# atmega328_tlc5940.net
KiCad netlist of a schematic drawn in EAGLE
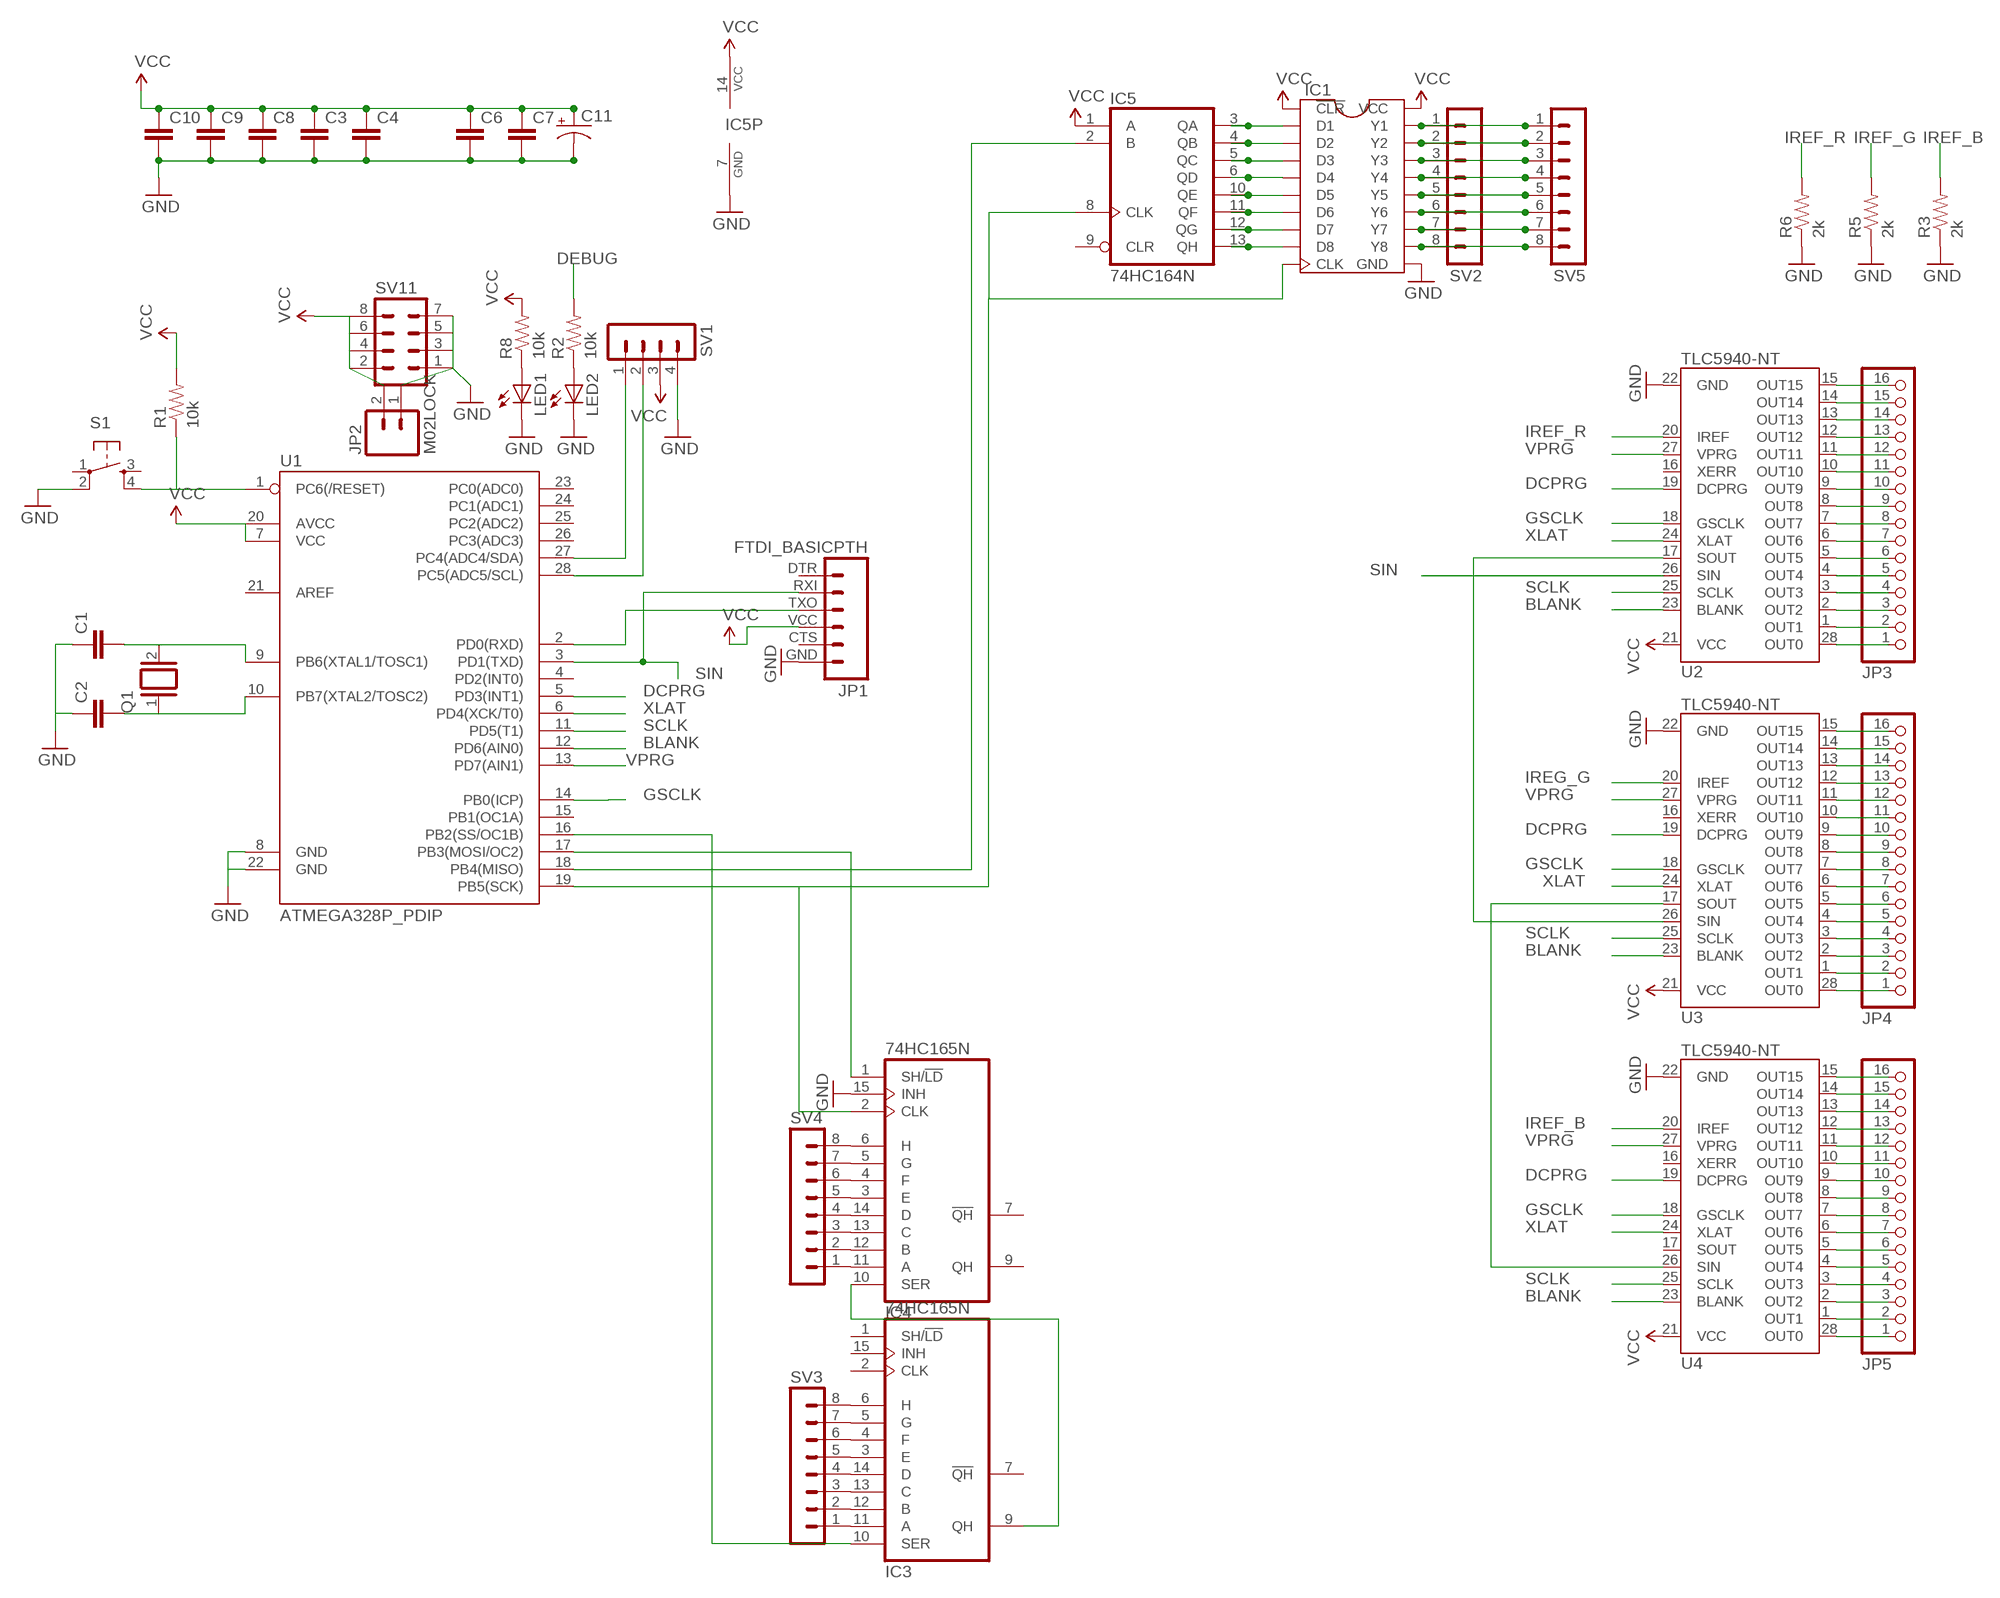
[diagram p0: schematic, sheet 1]

(export (version "E")
  (design (tool "Eeschema 10.0.6"))
  (components
    (comp (ref "C1")
      (value "CAPEZ")
      (footprint "eagle-import:CAP-PTH-SMALLEZ")
      (libsource (lib "eagle-import") (part "SparkFun-Passives_CAPEZ"))
    )
    (comp (ref "C2")
      (value "CAPEZ")
      (footprint "eagle-import:CAP-PTH-SMALLEZ")
      (libsource (lib "eagle-import") (part "SparkFun-Passives_CAPEZ"))
    )
    (comp (ref "C3")
      (value "CAPEZ")
      (footprint "eagle-import:CAP-PTH-SMALLEZ")
      (libsource (lib "eagle-import") (part "CAPEZ"))
    )
    (comp (ref "C4")
      (value "CAPEZ")
      (footprint "eagle-import:CAP-PTH-SMALLEZ")
      (libsource (lib "eagle-import") (part "CAPEZ"))
    )
    (comp (ref "C6")
      (value "CAPEZ")
      (footprint "eagle-import:CAP-PTH-SMALLEZ")
      (libsource (lib "eagle-import") (part "CAPEZ"))
    )
    (comp (ref "C7")
      (value "CAPEZ")
      (footprint "eagle-import:CAP-PTH-SMALLEZ")
      (libsource (lib "eagle-import") (part "CAPEZ"))
    )
    (comp (ref "C8")
      (value "CAPEZ")
      (footprint "eagle-import:CAP-PTH-SMALLEZ")
      (libsource (lib "eagle-import") (part "CAPEZ"))
    )
    (comp (ref "C9")
      (value "CAPEZ")
      (footprint "eagle-import:CAP-PTH-SMALLEZ")
      (libsource (lib "eagle-import") (part "CAPEZ"))
    )
    (comp (ref "C10")
      (value "CAPEZ")
      (footprint "eagle-import:CAP-PTH-SMALLEZ")
      (libsource (lib "eagle-import") (part "CAPEZ"))
    )
    (comp (ref "C11")
      (value "CPOL-USE3.5-8")
      (footprint "eagle-import:E3,5-8")
      (libsource (lib "eagle-import") (part "CPOL-USE3.5-8"))
    )
    (comp (ref "IC1")
      (value "IC-PACKAGE_DIL20S")
      (footprint "eagle-import:IC-PACKAGE_SOCKET-20")
      (libsource (lib "eagle-import") (part "IC-PACKAGE_DIL20S"))
    )
    (comp (ref "IC3")
      (value "74HC165N")
      (footprint "eagle-import:DIL16")
      (libsource (lib "eagle-import") (part "74165NHC"))
    )
    (comp (ref "IC4")
      (value "74HC165N")
      (footprint "eagle-import:DIL16")
      (libsource (lib "eagle-import") (part "74165NHC"))
    )
    (comp (ref "IC5")
      (value "74HC164N")
      (footprint "eagle-import:DIL14")
      (libsource (lib "eagle-import") (part "74164NHC"))
    )
    (comp (ref "JP1")
      (value "FTDI_BASICPTH")
      (footprint "eagle-import:FTDI_BASIC")
      (libsource (lib "eagle-import") (part "FTDI_BASICPTH"))
    )
    (comp (ref "JP2")
      (value "M02LOCK")
      (footprint "eagle-import:1X02_LOCK")
      (libsource (lib "eagle-import") (part "M02LOCK"))
    )
    (comp (ref "JP3")
      (value "PINHD-1X16")
      (footprint "eagle-import:1X16")
      (libsource (lib "eagle-import") (part "PINHD-1X16"))
    )
    (comp (ref "JP4")
      (value "PINHD-1X16")
      (footprint "eagle-import:1X16")
      (libsource (lib "eagle-import") (part "PINHD-1X16"))
    )
    (comp (ref "JP5")
      (value "PINHD-1X16")
      (footprint "eagle-import:1X16")
      (libsource (lib "eagle-import") (part "PINHD-1X16"))
    )
    (comp (ref "LED1")
      (value "LED5MM")
      (footprint "eagle-import:LED5MM")
      (libsource (lib "eagle-import") (part "LED5MM"))
    )
    (comp (ref "LED2")
      (value "LED5MM")
      (footprint "eagle-import:LED5MM")
      (libsource (lib "eagle-import") (part "LED5MM"))
    )
    (comp (ref "Q1")
      (value "XTAL/S")
      (footprint "eagle-import:QS")
      (libsource (lib "eagle-import") (part "XTAL/S"))
    )
    (comp (ref "R1")
      (value "10k")
      (footprint "eagle-import:AXIAL-0.3-KIT")
      (libsource (lib "eagle-import") (part "RESISTORKIT"))
    )
    (comp (ref "R2")
      (value "10k")
      (footprint "eagle-import:AXIAL-0.3-KIT")
      (libsource (lib "eagle-import") (part "RESISTORKIT"))
    )
    (comp (ref "R3")
      (value "2k")
      (footprint "eagle-import:AXIAL-0.3-KIT")
      (libsource (lib "eagle-import") (part "RESISTORKIT"))
    )
    (comp (ref "R5")
      (value "2k")
      (footprint "eagle-import:AXIAL-0.3-KIT")
      (libsource (lib "eagle-import") (part "RESISTORKIT"))
    )
    (comp (ref "R6")
      (value "2k")
      (footprint "eagle-import:AXIAL-0.3-KIT")
      (libsource (lib "eagle-import") (part "RESISTORKIT"))
    )
    (comp (ref "R8")
      (value "10k")
      (footprint "eagle-import:AXIAL-0.3-KIT")
      (libsource (lib "eagle-import") (part "RESISTORKIT"))
    )
    (comp (ref "S1")
      (value "TAC_SWITCHPTH")
      (footprint "eagle-import:TACTILE-PTH")
      (libsource (lib "eagle-import") (part "TAC_SWITCHPTH"))
    )
    (comp (ref "SV1")
      (value "MA04-1")
      (footprint "eagle-import:MA04-1")
      (libsource (lib "eagle-import") (part "MA04-1"))
    )
    (comp (ref "SV2")
      (value "MA08-1")
      (footprint "eagle-import:MA08-1")
      (libsource (lib "eagle-import") (part "MA08-1"))
    )
    (comp (ref "SV3")
      (value "MA08-1")
      (footprint "eagle-import:MA08-1")
      (libsource (lib "eagle-import") (part "MA08-1"))
    )
    (comp (ref "SV4")
      (value "MA08-1")
      (footprint "eagle-import:MA08-1")
      (libsource (lib "eagle-import") (part "MA08-1"))
    )
    (comp (ref "SV5")
      (value "MA08-1")
      (footprint "eagle-import:MA08-1")
      (libsource (lib "eagle-import") (part "MA08-1"))
    )
    (comp (ref "SV11")
      (value "MA04-2")
      (footprint "eagle-import:MA04-2")
      (libsource (lib "eagle-import") (part "MA04-2"))
    )
    (comp (ref "U1")
      (value "ATMEGA328P_PDIP")
      (footprint "eagle-import:DIL28-3")
      (libsource (lib "eagle-import") (part "ATMEGA328P_PDIP"))
    )
    (comp (ref "U2")
      (value "TLC5940-NT")
      (footprint "eagle-import:DIL28-3")
      (libsource (lib "eagle-import") (part "TLC5940-NT"))
    )
    (comp (ref "U3")
      (value "TLC5940-NT")
      (footprint "eagle-import:DIL28-3")
      (libsource (lib "eagle-import") (part "TLC5940-NT"))
    )
    (comp (ref "U4")
      (value "TLC5940-NT")
      (footprint "eagle-import:DIL28-3")
      (libsource (lib "eagle-import") (part "TLC5940-NT"))
    )
  )
  (nets
    (net (code "1") (name "/BLANK") (class "Default")
      (node (ref "U1") (pin "12") (pinfunction "PD6(AIN0)_12") (pintype "bidirectional"))
      (node (ref "U2") (pin "23") (pinfunction "BLANK_23") (pintype "bidirectional"))
      (node (ref "U3") (pin "23") (pinfunction "BLANK_23") (pintype "bidirectional"))
      (node (ref "U4") (pin "23") (pinfunction "BLANK_23") (pintype "bidirectional"))
    )
    (net (code "2") (name "/DCPRG") (class "Default")
      (node (ref "U1") (pin "5") (pinfunction "PD3(INT1)_5") (pintype "bidirectional"))
      (node (ref "U2") (pin "19") (pinfunction "DCPRG_19") (pintype "bidirectional"))
      (node (ref "U3") (pin "19") (pinfunction "DCPRG_19") (pintype "bidirectional"))
      (node (ref "U4") (pin "19") (pinfunction "DCPRG_19") (pintype "bidirectional"))
    )
    (net (code "3") (name "/DEBUG") (class "Default")
      (node (ref "R2") (pin "P$2") (pinfunction "2_P$2") (pintype "passive"))
    )
    (net (code "4") (name "/GSCLK") (class "Default")
      (node (ref "U1") (pin "14") (pinfunction "PB0(ICP)_14") (pintype "bidirectional"))
      (node (ref "U2") (pin "18") (pinfunction "GSCLK_18") (pintype "bidirectional"))
      (node (ref "U3") (pin "18") (pinfunction "GSCLK_18") (pintype "bidirectional"))
      (node (ref "U4") (pin "18") (pinfunction "GSCLK_18") (pintype "bidirectional"))
    )
    (net (code "5") (name "/IREF_B") (class "Default")
      (node (ref "R3") (pin "P$2") (pinfunction "2_P$2") (pintype "passive"))
      (node (ref "U4") (pin "20") (pinfunction "IREF_20") (pintype "bidirectional"))
    )
    (net (code "6") (name "/IREF_G") (class "Default")
      (node (ref "R5") (pin "P$2") (pinfunction "2_P$2") (pintype "passive"))
    )
    (net (code "7") (name "/IREF_R") (class "Default")
      (node (ref "R6") (pin "P$2") (pinfunction "2_P$2") (pintype "passive"))
      (node (ref "U2") (pin "20") (pinfunction "IREF_20") (pintype "bidirectional"))
    )
    (net (code "8") (name "/IREG_G") (class "Default")
      (node (ref "U3") (pin "20") (pinfunction "IREF_20") (pintype "bidirectional"))
    )
    (net (code "9") (name "/SCLK") (class "Default")
      (node (ref "U1") (pin "11") (pinfunction "PD5(T1)_11") (pintype "bidirectional"))
      (node (ref "U2") (pin "25") (pinfunction "SCLK_25") (pintype "bidirectional"))
      (node (ref "U3") (pin "25") (pinfunction "SCLK_25") (pintype "bidirectional"))
      (node (ref "U4") (pin "25") (pinfunction "SCLK_25") (pintype "bidirectional"))
    )
    (net (code "10") (name "/SIN") (class "Default")
      (node (ref "JP1") (pin "RXI") (pinfunction "2_RXI") (pintype "passive"))
      (node (ref "U1") (pin "3") (pinfunction "PD1(TXD)_3") (pintype "bidirectional"))
      (node (ref "U2") (pin "26") (pinfunction "SIN_26") (pintype "bidirectional"))
    )
    (net (code "11") (name "/VPRG") (class "Default")
      (node (ref "U1") (pin "13") (pinfunction "PD7(AIN1)_13") (pintype "bidirectional"))
      (node (ref "U2") (pin "27") (pinfunction "VPRG_27") (pintype "bidirectional"))
      (node (ref "U3") (pin "27") (pinfunction "VPRG_27") (pintype "bidirectional"))
      (node (ref "U4") (pin "27") (pinfunction "VPRG_27") (pintype "bidirectional"))
    )
    (net (code "12") (name "/XLAT") (class "Default")
      (node (ref "U1") (pin "6") (pinfunction "PD4(XCK/T0)_6") (pintype "bidirectional"))
      (node (ref "U2") (pin "24") (pinfunction "XLAT_24") (pintype "bidirectional"))
      (node (ref "U3") (pin "24") (pinfunction "XLAT_24") (pintype "bidirectional"))
      (node (ref "U4") (pin "24") (pinfunction "XLAT_24") (pintype "bidirectional"))
    )
    (net (code "13") (name "GND") (class "Default")
      (node (ref "C1") (pin "1") (pinfunction "1_1") (pintype "passive"))
      (node (ref "C10") (pin "2") (pinfunction "2_2") (pintype "passive"))
      (node (ref "C11") (pin "-") (pinfunction "-_-") (pintype "passive"))
      (node (ref "C2") (pin "1") (pinfunction "1_1") (pintype "passive"))
      (node (ref "C3") (pin "2") (pinfunction "2_2") (pintype "passive"))
      (node (ref "C4") (pin "2") (pinfunction "2_2") (pintype "passive"))
      (node (ref "C6") (pin "2") (pinfunction "2_2") (pintype "passive"))
      (node (ref "C7") (pin "2") (pinfunction "2_2") (pintype "passive"))
      (node (ref "C8") (pin "2") (pinfunction "2_2") (pintype "passive"))
      (node (ref "C9") (pin "2") (pinfunction "2_2") (pintype "passive"))
      (node (ref "IC1") (pin "11") (pinfunction "GND_11") (pintype "power_in"))
      (node (ref "IC4") (pin "15") (pinfunction "INH_15") (pintype "input"))
      (node (ref "IC5") (pin "7") (pinfunction "GND_7") (pintype "power_in"))
      (node (ref "JP1") (pin "GND") (pinfunction "6_GND") (pintype "passive"))
      (node (ref "JP2") (pin "1") (pinfunction "1_1") (pintype "passive"))
      (node (ref "LED1") (pin "K") (pinfunction "C_K") (pintype "passive"))
      (node (ref "LED2") (pin "K") (pinfunction "C_K") (pintype "passive"))
      (node (ref "R3") (pin "P$1") (pinfunction "1_P$1") (pintype "passive"))
      (node (ref "R5") (pin "P$1") (pinfunction "1_P$1") (pintype "passive"))
      (node (ref "R6") (pin "P$1") (pinfunction "1_P$1") (pintype "passive"))
      (node (ref "S1") (pin "2") (pinfunction "2_2") (pintype "passive"))
      (node (ref "SV1") (pin "4") (pinfunction "4_4") (pintype "passive"))
      (node (ref "SV11") (pin "1") (pinfunction "1_1") (pintype "passive"))
      (node (ref "SV11") (pin "3") (pinfunction "3_3") (pintype "passive"))
      (node (ref "SV11") (pin "5") (pinfunction "5_5") (pintype "passive"))
      (node (ref "SV11") (pin "7") (pinfunction "7_7") (pintype "passive"))
      (node (ref "U1") (pin "22") (pinfunction "GND_22") (pintype "bidirectional"))
      (node (ref "U1") (pin "8") (pinfunction "GND_8") (pintype "bidirectional"))
      (node (ref "U2") (pin "22") (pinfunction "GND_22") (pintype "bidirectional"))
      (node (ref "U3") (pin "22") (pinfunction "GND_22") (pintype "bidirectional"))
      (node (ref "U4") (pin "22") (pinfunction "GND_22") (pintype "bidirectional"))
    )
    (net (code "14") (name "Net-(IC1-CLK)") (class "Default")
      (node (ref "IC1") (pin "10") (pinfunction "CLK_10") (pintype "input"))
      (node (ref "IC4") (pin "2") (pinfunction "CLK_2") (pintype "input"))
      (node (ref "IC5") (pin "8") (pinfunction "CLK_8") (pintype "input"))
      (node (ref "U1") (pin "19") (pinfunction "PB5(SCK)_19") (pintype "bidirectional"))
    )
    (net (code "15") (name "Net-(IC1-D1)") (class "Default")
      (node (ref "IC1") (pin "2") (pinfunction "D1_2") (pintype "input"))
      (node (ref "IC5") (pin "3") (pinfunction "QA_3") (pintype "output"))
    )
    (net (code "16") (name "Net-(IC1-D2)") (class "Default")
      (node (ref "IC1") (pin "3") (pinfunction "D2_3") (pintype "input"))
      (node (ref "IC5") (pin "4") (pinfunction "QB_4") (pintype "output"))
    )
    (net (code "17") (name "Net-(IC1-D3)") (class "Default")
      (node (ref "IC1") (pin "4") (pinfunction "D3_4") (pintype "input"))
      (node (ref "IC5") (pin "5") (pinfunction "QC_5") (pintype "output"))
    )
    (net (code "18") (name "Net-(IC1-D4)") (class "Default")
      (node (ref "IC1") (pin "5") (pinfunction "D4_5") (pintype "input"))
      (node (ref "IC5") (pin "6") (pinfunction "QD_6") (pintype "output"))
    )
    (net (code "19") (name "Net-(IC1-D5)") (class "Default")
      (node (ref "IC1") (pin "6") (pinfunction "D5_6") (pintype "input"))
      (node (ref "IC5") (pin "10") (pinfunction "QE_10") (pintype "output"))
    )
    (net (code "20") (name "Net-(IC1-D6)") (class "Default")
      (node (ref "IC1") (pin "7") (pinfunction "D6_7") (pintype "input"))
      (node (ref "IC5") (pin "11") (pinfunction "QF_11") (pintype "output"))
    )
    (net (code "21") (name "Net-(IC1-D7)") (class "Default")
      (node (ref "IC1") (pin "8") (pinfunction "D7_8") (pintype "input"))
      (node (ref "IC5") (pin "12") (pinfunction "QG_12") (pintype "output"))
    )
    (net (code "22") (name "Net-(IC1-D8)") (class "Default")
      (node (ref "IC1") (pin "9") (pinfunction "D8_9") (pintype "input"))
      (node (ref "IC5") (pin "13") (pinfunction "QH_13") (pintype "output"))
    )
    (net (code "23") (name "Net-(IC1-Y1)") (class "Default")
      (node (ref "IC1") (pin "19") (pinfunction "Y1_19") (pintype "output"))
      (node (ref "SV2") (pin "1") (pinfunction "1_1") (pintype "passive"))
      (node (ref "SV5") (pin "1") (pinfunction "1_1") (pintype "passive"))
    )
    (net (code "24") (name "Net-(IC1-Y2)") (class "Default")
      (node (ref "IC1") (pin "18") (pinfunction "Y2_18") (pintype "output"))
      (node (ref "SV2") (pin "2") (pinfunction "2_2") (pintype "passive"))
      (node (ref "SV5") (pin "2") (pinfunction "2_2") (pintype "passive"))
    )
    (net (code "25") (name "Net-(IC1-Y3)") (class "Default")
      (node (ref "IC1") (pin "17") (pinfunction "Y3_17") (pintype "output"))
      (node (ref "SV2") (pin "3") (pinfunction "3_3") (pintype "passive"))
      (node (ref "SV5") (pin "3") (pinfunction "3_3") (pintype "passive"))
    )
    (net (code "26") (name "Net-(IC1-Y4)") (class "Default")
      (node (ref "IC1") (pin "16") (pinfunction "Y4_16") (pintype "output"))
      (node (ref "SV2") (pin "4") (pinfunction "4_4") (pintype "passive"))
      (node (ref "SV5") (pin "4") (pinfunction "4_4") (pintype "passive"))
    )
    (net (code "27") (name "Net-(IC1-Y5)") (class "Default")
      (node (ref "IC1") (pin "15") (pinfunction "Y5_15") (pintype "output"))
      (node (ref "SV2") (pin "5") (pinfunction "5_5") (pintype "passive"))
      (node (ref "SV5") (pin "5") (pinfunction "5_5") (pintype "passive"))
    )
    (net (code "28") (name "Net-(IC1-Y6)") (class "Default")
      (node (ref "IC1") (pin "14") (pinfunction "Y6_14") (pintype "output"))
      (node (ref "SV2") (pin "6") (pinfunction "6_6") (pintype "passive"))
      (node (ref "SV5") (pin "6") (pinfunction "6_6") (pintype "passive"))
    )
    (net (code "29") (name "Net-(IC1-Y7)") (class "Default")
      (node (ref "IC1") (pin "13") (pinfunction "Y7_13") (pintype "output"))
      (node (ref "SV2") (pin "7") (pinfunction "7_7") (pintype "passive"))
      (node (ref "SV5") (pin "7") (pinfunction "7_7") (pintype "passive"))
    )
    (net (code "30") (name "Net-(IC1-Y8)") (class "Default")
      (node (ref "IC1") (pin "12") (pinfunction "Y8_12") (pintype "output"))
      (node (ref "SV2") (pin "8") (pinfunction "8_8") (pintype "passive"))
      (node (ref "SV5") (pin "8") (pinfunction "8_8") (pintype "passive"))
    )
    (net (code "31") (name "Net-(IC3A-A)") (class "Default")
      (node (ref "IC3") (pin "11") (pinfunction "A_11") (pintype "input"))
      (node (ref "SV3") (pin "1") (pinfunction "1_1") (pintype "passive"))
    )
    (net (code "32") (name "Net-(IC3A-B)") (class "Default")
      (node (ref "IC3") (pin "12") (pinfunction "B_12") (pintype "input"))
      (node (ref "SV3") (pin "2") (pinfunction "2_2") (pintype "passive"))
    )
    (net (code "33") (name "Net-(IC3A-C)") (class "Default")
      (node (ref "IC3") (pin "13") (pinfunction "C_13") (pintype "input"))
      (node (ref "SV3") (pin "3") (pinfunction "3_3") (pintype "passive"))
    )
    (net (code "34") (name "Net-(IC3A-D)") (class "Default")
      (node (ref "IC3") (pin "14") (pinfunction "D_14") (pintype "input"))
      (node (ref "SV3") (pin "4") (pinfunction "4_4") (pintype "passive"))
    )
    (net (code "35") (name "Net-(IC3A-E)") (class "Default")
      (node (ref "IC3") (pin "3") (pinfunction "E_3") (pintype "input"))
      (node (ref "SV3") (pin "5") (pinfunction "5_5") (pintype "passive"))
    )
    (net (code "36") (name "Net-(IC3A-F)") (class "Default")
      (node (ref "IC3") (pin "4") (pinfunction "F_4") (pintype "input"))
      (node (ref "SV3") (pin "6") (pinfunction "6_6") (pintype "passive"))
    )
    (net (code "37") (name "Net-(IC3A-G)") (class "Default")
      (node (ref "IC3") (pin "5") (pinfunction "G_5") (pintype "input"))
      (node (ref "SV3") (pin "7") (pinfunction "7_7") (pintype "passive"))
    )
    (net (code "38") (name "Net-(IC3A-H)") (class "Default")
      (node (ref "IC3") (pin "6") (pinfunction "H_6") (pintype "input"))
      (node (ref "SV3") (pin "8") (pinfunction "8_8") (pintype "passive"))
    )
    (net (code "39") (name "Net-(IC3A-QH)") (class "Default")
      (node (ref "IC3") (pin "9") (pinfunction "QH_9") (pintype "output"))
      (node (ref "IC4") (pin "10") (pinfunction "SER_10") (pintype "input"))
    )
    (net (code "40") (name "Net-(IC3A-SER)") (class "Default")
      (node (ref "IC3") (pin "10") (pinfunction "SER_10") (pintype "input"))
      (node (ref "U1") (pin "16") (pinfunction "PB2(SS/OC1B)_16") (pintype "bidirectional"))
    )
    (net (code "41") (name "Net-(IC4A-A)") (class "Default")
      (node (ref "IC4") (pin "11") (pinfunction "A_11") (pintype "input"))
      (node (ref "SV4") (pin "1") (pinfunction "1_1") (pintype "passive"))
    )
    (net (code "42") (name "Net-(IC4A-B)") (class "Default")
      (node (ref "IC4") (pin "12") (pinfunction "B_12") (pintype "input"))
      (node (ref "SV4") (pin "2") (pinfunction "2_2") (pintype "passive"))
    )
    (net (code "43") (name "Net-(IC4A-C)") (class "Default")
      (node (ref "IC4") (pin "13") (pinfunction "C_13") (pintype "input"))
      (node (ref "SV4") (pin "3") (pinfunction "3_3") (pintype "passive"))
    )
    (net (code "44") (name "Net-(IC4A-D)") (class "Default")
      (node (ref "IC4") (pin "14") (pinfunction "D_14") (pintype "input"))
      (node (ref "SV4") (pin "4") (pinfunction "4_4") (pintype "passive"))
    )
    (net (code "45") (name "Net-(IC4A-E)") (class "Default")
      (node (ref "IC4") (pin "3") (pinfunction "E_3") (pintype "input"))
      (node (ref "SV4") (pin "5") (pinfunction "5_5") (pintype "passive"))
    )
    (net (code "46") (name "Net-(IC4A-F)") (class "Default")
      (node (ref "IC4") (pin "4") (pinfunction "F_4") (pintype "input"))
      (node (ref "SV4") (pin "6") (pinfunction "6_6") (pintype "passive"))
    )
    (net (code "47") (name "Net-(IC4A-G)") (class "Default")
      (node (ref "IC4") (pin "5") (pinfunction "G_5") (pintype "input"))
      (node (ref "SV4") (pin "7") (pinfunction "7_7") (pintype "passive"))
    )
    (net (code "48") (name "Net-(IC4A-H)") (class "Default")
      (node (ref "IC4") (pin "6") (pinfunction "H_6") (pintype "input"))
      (node (ref "SV4") (pin "8") (pinfunction "8_8") (pintype "passive"))
    )
    (net (code "49") (name "Net-(IC4A-SH{slash}~{LD})") (class "Default")
      (node (ref "IC4") (pin "1") (pinfunction "SH/~{LD}_1") (pintype "input"))
      (node (ref "U1") (pin "17") (pinfunction "PB3(MOSI/OC2)_17") (pintype "bidirectional"))
    )
    (net (code "50") (name "Net-(IC5A-B)") (class "Default")
      (node (ref "IC5") (pin "2") (pinfunction "B_2") (pintype "input"))
      (node (ref "U1") (pin "18") (pinfunction "PB4(MISO)_18") (pintype "bidirectional"))
    )
    (net (code "51") (name "Net-(JP1-3)") (class "Default")
      (node (ref "JP1") (pin "TXO") (pinfunction "3_TXO") (pintype "passive"))
      (node (ref "U1") (pin "2") (pinfunction "PD0(RXD)_2") (pintype "bidirectional"))
    )
    (net (code "52") (name "Net-(R1-1)") (class "Default")
      (node (ref "R1") (pin "P$1") (pinfunction "1_P$1") (pintype "passive"))
      (node (ref "S1") (pin "4") (pinfunction "4_4") (pintype "passive"))
      (node (ref "U1") (pin "1") (pinfunction "PC6(/RESET)_1") (pintype "bidirectional"))
    )
    (net (code "53") (name "Net-(R2-1)") (class "Default")
      (node (ref "LED2") (pin "A") (pinfunction "A_A") (pintype "passive"))
      (node (ref "R2") (pin "P$1") (pinfunction "1_P$1") (pintype "passive"))
    )
    (net (code "54") (name "Net-(R8-1)") (class "Default")
      (node (ref "LED1") (pin "A") (pinfunction "A_A") (pintype "passive"))
      (node (ref "R8") (pin "P$1") (pinfunction "1_P$1") (pintype "passive"))
    )
    (net (code "55") (name "Net-(U1-PB6(XTAL1{slash}TOSC1))") (class "Default")
      (node (ref "C1") (pin "2") (pinfunction "2_2") (pintype "passive"))
      (node (ref "Q1") (pin "2") (pinfunction "2_2") (pintype "passive"))
      (node (ref "U1") (pin "9") (pinfunction "PB6(XTAL1/TOSC1)_9") (pintype "bidirectional"))
    )
    (net (code "56") (name "Net-(U1-PB7(XTAL2{slash}TOSC2))") (class "Default")
      (node (ref "C2") (pin "2") (pinfunction "2_2") (pintype "passive"))
      (node (ref "Q1") (pin "1") (pinfunction "1_1") (pintype "passive"))
      (node (ref "U1") (pin "10") (pinfunction "PB7(XTAL2/TOSC2)_10") (pintype "bidirectional"))
    )
    (net (code "57") (name "Net-(U1-PC4(ADC4{slash}SDA))") (class "Default")
      (node (ref "SV1") (pin "1") (pinfunction "1_1") (pintype "passive"))
      (node (ref "U1") (pin "27") (pinfunction "PC4(ADC4/SDA)_27") (pintype "bidirectional"))
    )
    (net (code "58") (name "Net-(U1-PC5(ADC5{slash}SCL))") (class "Default")
      (node (ref "SV1") (pin "2") (pinfunction "2_2") (pintype "passive"))
      (node (ref "U1") (pin "28") (pinfunction "PC5(ADC5/SCL)_28") (pintype "bidirectional"))
    )
    (net (code "59") (name "Net-(U2-OUT0)") (class "Default")
      (node (ref "JP3") (pin "1") (pinfunction "1_1") (pintype "passive"))
      (node (ref "U2") (pin "28") (pinfunction "OUT0_28") (pintype "bidirectional"))
    )
    (net (code "60") (name "Net-(U2-OUT1)") (class "Default")
      (node (ref "JP3") (pin "2") (pinfunction "2_2") (pintype "passive"))
      (node (ref "U2") (pin "1") (pinfunction "OUT1_1") (pintype "bidirectional"))
    )
    (net (code "61") (name "Net-(U2-OUT2)") (class "Default")
      (node (ref "JP3") (pin "3") (pinfunction "3_3") (pintype "passive"))
      (node (ref "U2") (pin "2") (pinfunction "OUT2_2") (pintype "bidirectional"))
    )
    (net (code "62") (name "Net-(U2-OUT3)") (class "Default")
      (node (ref "JP3") (pin "4") (pinfunction "4_4") (pintype "passive"))
      (node (ref "U2") (pin "3") (pinfunction "OUT3_3") (pintype "bidirectional"))
    )
    (net (code "63") (name "Net-(U2-OUT4)") (class "Default")
      (node (ref "JP3") (pin "5") (pinfunction "5_5") (pintype "passive"))
      (node (ref "U2") (pin "4") (pinfunction "OUT4_4") (pintype "bidirectional"))
    )
    (net (code "64") (name "Net-(U2-OUT5)") (class "Default")
      (node (ref "JP3") (pin "6") (pinfunction "6_6") (pintype "passive"))
      (node (ref "U2") (pin "5") (pinfunction "OUT5_5") (pintype "bidirectional"))
    )
    (net (code "65") (name "Net-(U2-OUT6)") (class "Default")
      (node (ref "JP3") (pin "7") (pinfunction "7_7") (pintype "passive"))
      (node (ref "U2") (pin "6") (pinfunction "OUT6_6") (pintype "bidirectional"))
    )
    (net (code "66") (name "Net-(U2-OUT7)") (class "Default")
      (node (ref "JP3") (pin "8") (pinfunction "8_8") (pintype "passive"))
      (node (ref "U2") (pin "7") (pinfunction "OUT7_7") (pintype "bidirectional"))
    )
    (net (code "67") (name "Net-(U2-OUT8)") (class "Default")
      (node (ref "JP3") (pin "9") (pinfunction "9_9") (pintype "passive"))
      (node (ref "U2") (pin "8") (pinfunction "OUT8_8") (pintype "bidirectional"))
    )
    (net (code "68") (name "Net-(U2-OUT9)") (class "Default")
      (node (ref "JP3") (pin "10") (pinfunction "10_10") (pintype "passive"))
      (node (ref "U2") (pin "9") (pinfunction "OUT9_9") (pintype "bidirectional"))
    )
    (net (code "69") (name "Net-(U2-OUT10)") (class "Default")
      (node (ref "JP3") (pin "11") (pinfunction "11_11") (pintype "passive"))
      (node (ref "U2") (pin "10") (pinfunction "OUT10_10") (pintype "bidirectional"))
    )
    (net (code "70") (name "Net-(U2-OUT11)") (class "Default")
      (node (ref "JP3") (pin "12") (pinfunction "12_12") (pintype "passive"))
      (node (ref "U2") (pin "11") (pinfunction "OUT11_11") (pintype "bidirectional"))
    )
    (net (code "71") (name "Net-(U2-OUT12)") (class "Default")
      (node (ref "JP3") (pin "13") (pinfunction "13_13") (pintype "passive"))
      (node (ref "U2") (pin "12") (pinfunction "OUT12_12") (pintype "bidirectional"))
    )
    (net (code "72") (name "Net-(U2-OUT13)") (class "Default")
      (node (ref "JP3") (pin "14") (pinfunction "14_14") (pintype "passive"))
      (node (ref "U2") (pin "13") (pinfunction "OUT13_13") (pintype "bidirectional"))
    )
    (net (code "73") (name "Net-(U2-OUT14)") (class "Default")
      (node (ref "JP3") (pin "15") (pinfunction "15_15") (pintype "passive"))
      (node (ref "U2") (pin "14") (pinfunction "OUT14_14") (pintype "bidirectional"))
    )
    (net (code "74") (name "Net-(U2-OUT15)") (class "Default")
      (node (ref "JP3") (pin "16") (pinfunction "16_16") (pintype "passive"))
      (node (ref "U2") (pin "15") (pinfunction "OUT15_15") (pintype "bidirectional"))
    )
    (net (code "75") (name "Net-(U2-SOUT)") (class "Default")
      (node (ref "U2") (pin "17") (pinfunction "SOUT_17") (pintype "bidirectional"))
      (node (ref "U3") (pin "26") (pinfunction "SIN_26") (pintype "bidirectional"))
    )
    (net (code "76") (name "Net-(U3-OUT0)") (class "Default")
      (node (ref "JP4") (pin "1") (pinfunction "1_1") (pintype "passive"))
      (node (ref "U3") (pin "28") (pinfunction "OUT0_28") (pintype "bidirectional"))
    )
    (net (code "77") (name "Net-(U3-OUT1)") (class "Default")
      (node (ref "JP4") (pin "2") (pinfunction "2_2") (pintype "passive"))
      (node (ref "U3") (pin "1") (pinfunction "OUT1_1") (pintype "bidirectional"))
    )
    (net (code "78") (name "Net-(U3-OUT2)") (class "Default")
      (node (ref "JP4") (pin "3") (pinfunction "3_3") (pintype "passive"))
      (node (ref "U3") (pin "2") (pinfunction "OUT2_2") (pintype "bidirectional"))
    )
    (net (code "79") (name "Net-(U3-OUT3)") (class "Default")
      (node (ref "JP4") (pin "4") (pinfunction "4_4") (pintype "passive"))
      (node (ref "U3") (pin "3") (pinfunction "OUT3_3") (pintype "bidirectional"))
    )
    (net (code "80") (name "Net-(U3-OUT4)") (class "Default")
      (node (ref "JP4") (pin "5") (pinfunction "5_5") (pintype "passive"))
      (node (ref "U3") (pin "4") (pinfunction "OUT4_4") (pintype "bidirectional"))
    )
    (net (code "81") (name "Net-(U3-OUT5)") (class "Default")
      (node (ref "JP4") (pin "6") (pinfunction "6_6") (pintype "passive"))
      (node (ref "U3") (pin "5") (pinfunction "OUT5_5") (pintype "bidirectional"))
    )
    (net (code "82") (name "Net-(U3-OUT6)") (class "Default")
      (node (ref "JP4") (pin "7") (pinfunction "7_7") (pintype "passive"))
      (node (ref "U3") (pin "6") (pinfunction "OUT6_6") (pintype "bidirectional"))
    )
    (net (code "83") (name "Net-(U3-OUT7)") (class "Default")
      (node (ref "JP4") (pin "8") (pinfunction "8_8") (pintype "passive"))
      (node (ref "U3") (pin "7") (pinfunction "OUT7_7") (pintype "bidirectional"))
    )
    (net (code "84") (name "Net-(U3-OUT8)") (class "Default")
      (node (ref "JP4") (pin "9") (pinfunction "9_9") (pintype "passive"))
      (node (ref "U3") (pin "8") (pinfunction "OUT8_8") (pintype "bidirectional"))
    )
    (net (code "85") (name "Net-(U3-OUT9)") (class "Default")
      (node (ref "JP4") (pin "10") (pinfunction "10_10") (pintype "passive"))
      (node (ref "U3") (pin "9") (pinfunction "OUT9_9") (pintype "bidirectional"))
    )
    (net (code "86") (name "Net-(U3-OUT10)") (class "Default")
      (node (ref "JP4") (pin "11") (pinfunction "11_11") (pintype "passive"))
      (node (ref "U3") (pin "10") (pinfunction "OUT10_10") (pintype "bidirectional"))
    )
    (net (code "87") (name "Net-(U3-OUT11)") (class "Default")
      (node (ref "JP4") (pin "12") (pinfunction "12_12") (pintype "passive"))
      (node (ref "U3") (pin "11") (pinfunction "OUT11_11") (pintype "bidirectional"))
    )
    (net (code "88") (name "Net-(U3-OUT12)") (class "Default")
      (node (ref "JP4") (pin "13") (pinfunction "13_13") (pintype "passive"))
      (node (ref "U3") (pin "12") (pinfunction "OUT12_12") (pintype "bidirectional"))
    )
    (net (code "89") (name "Net-(U3-OUT13)") (class "Default")
      (node (ref "JP4") (pin "14") (pinfunction "14_14") (pintype "passive"))
      (node (ref "U3") (pin "13") (pinfunction "OUT13_13") (pintype "bidirectional"))
    )
    (net (code "90") (name "Net-(U3-OUT14)") (class "Default")
      (node (ref "JP4") (pin "15") (pinfunction "15_15") (pintype "passive"))
      (node (ref "U3") (pin "14") (pinfunction "OUT14_14") (pintype "bidirectional"))
    )
    (net (code "91") (name "Net-(U3-OUT15)") (class "Default")
      (node (ref "JP4") (pin "16") (pinfunction "16_16") (pintype "passive"))
      (node (ref "U3") (pin "15") (pinfunction "OUT15_15") (pintype "bidirectional"))
    )
    (net (code "92") (name "Net-(U3-SOUT)") (class "Default")
      (node (ref "U3") (pin "17") (pinfunction "SOUT_17") (pintype "bidirectional"))
      (node (ref "U4") (pin "26") (pinfunction "SIN_26") (pintype "bidirectional"))
    )
    (net (code "93") (name "Net-(U4-OUT0)") (class "Default")
      (node (ref "JP5") (pin "1") (pinfunction "1_1") (pintype "passive"))
      (node (ref "U4") (pin "28") (pinfunction "OUT0_28") (pintype "bidirectional"))
    )
    (net (code "94") (name "Net-(U4-OUT1)") (class "Default")
      (node (ref "JP5") (pin "2") (pinfunction "2_2") (pintype "passive"))
      (node (ref "U4") (pin "1") (pinfunction "OUT1_1") (pintype "bidirectional"))
    )
    (net (code "95") (name "Net-(U4-OUT2)") (class "Default")
      (node (ref "JP5") (pin "3") (pinfunction "3_3") (pintype "passive"))
      (node (ref "U4") (pin "2") (pinfunction "OUT2_2") (pintype "bidirectional"))
    )
    (net (code "96") (name "Net-(U4-OUT3)") (class "Default")
      (node (ref "JP5") (pin "4") (pinfunction "4_4") (pintype "passive"))
      (node (ref "U4") (pin "3") (pinfunction "OUT3_3") (pintype "bidirectional"))
    )
    (net (code "97") (name "Net-(U4-OUT4)") (class "Default")
      (node (ref "JP5") (pin "5") (pinfunction "5_5") (pintype "passive"))
      (node (ref "U4") (pin "4") (pinfunction "OUT4_4") (pintype "bidirectional"))
    )
    (net (code "98") (name "Net-(U4-OUT5)") (class "Default")
      (node (ref "JP5") (pin "6") (pinfunction "6_6") (pintype "passive"))
      (node (ref "U4") (pin "5") (pinfunction "OUT5_5") (pintype "bidirectional"))
    )
    (net (code "99") (name "Net-(U4-OUT6)") (class "Default")
      (node (ref "JP5") (pin "7") (pinfunction "7_7") (pintype "passive"))
      (node (ref "U4") (pin "6") (pinfunction "OUT6_6") (pintype "bidirectional"))
    )
    (net (code "100") (name "Net-(U4-OUT7)") (class "Default")
      (node (ref "JP5") (pin "8") (pinfunction "8_8") (pintype "passive"))
      (node (ref "U4") (pin "7") (pinfunction "OUT7_7") (pintype "bidirectional"))
    )
    (net (code "101") (name "Net-(U4-OUT8)") (class "Default")
      (node (ref "JP5") (pin "9") (pinfunction "9_9") (pintype "passive"))
      (node (ref "U4") (pin "8") (pinfunction "OUT8_8") (pintype "bidirectional"))
    )
    (net (code "102") (name "Net-(U4-OUT9)") (class "Default")
      (node (ref "JP5") (pin "10") (pinfunction "10_10") (pintype "passive"))
      (node (ref "U4") (pin "9") (pinfunction "OUT9_9") (pintype "bidirectional"))
    )
    (net (code "103") (name "Net-(U4-OUT10)") (class "Default")
      (node (ref "JP5") (pin "11") (pinfunction "11_11") (pintype "passive"))
      (node (ref "U4") (pin "10") (pinfunction "OUT10_10") (pintype "bidirectional"))
    )
    (net (code "104") (name "Net-(U4-OUT11)") (class "Default")
      (node (ref "JP5") (pin "12") (pinfunction "12_12") (pintype "passive"))
      (node (ref "U4") (pin "11") (pinfunction "OUT11_11") (pintype "bidirectional"))
    )
    (net (code "105") (name "Net-(U4-OUT12)") (class "Default")
      (node (ref "JP5") (pin "13") (pinfunction "13_13") (pintype "passive"))
      (node (ref "U4") (pin "12") (pinfunction "OUT12_12") (pintype "bidirectional"))
    )
    (net (code "106") (name "Net-(U4-OUT13)") (class "Default")
      (node (ref "JP5") (pin "14") (pinfunction "14_14") (pintype "passive"))
      (node (ref "U4") (pin "13") (pinfunction "OUT13_13") (pintype "bidirectional"))
    )
    (net (code "107") (name "Net-(U4-OUT14)") (class "Default")
      (node (ref "JP5") (pin "15") (pinfunction "15_15") (pintype "passive"))
      (node (ref "U4") (pin "14") (pinfunction "OUT14_14") (pintype "bidirectional"))
    )
    (net (code "108") (name "Net-(U4-OUT15)") (class "Default")
      (node (ref "JP5") (pin "16") (pinfunction "16_16") (pintype "passive"))
      (node (ref "U4") (pin "15") (pinfunction "OUT15_15") (pintype "bidirectional"))
    )
    (net (code "109") (name "VCC") (class "Default")
      (node (ref "C10") (pin "1") (pinfunction "1_1") (pintype "passive"))
      (node (ref "C11") (pin "+") (pinfunction "+_+") (pintype "passive"))
      (node (ref "C3") (pin "1") (pinfunction "1_1") (pintype "passive"))
      (node (ref "C4") (pin "1") (pinfunction "1_1") (pintype "passive"))
      (node (ref "C6") (pin "1") (pinfunction "1_1") (pintype "passive"))
      (node (ref "C7") (pin "1") (pinfunction "1_1") (pintype "passive"))
      (node (ref "C8") (pin "1") (pinfunction "1_1") (pintype "passive"))
      (node (ref "C9") (pin "1") (pinfunction "1_1") (pintype "passive"))
      (node (ref "IC1") (pin "1") (pinfunction "~{CLR}_1") (pintype "input"))
      (node (ref "IC1") (pin "20") (pinfunction "VCC_20") (pintype "power_in"))
      (node (ref "IC5") (pin "1") (pinfunction "A_1") (pintype "input"))
      (node (ref "IC5") (pin "14") (pinfunction "VCC_14") (pintype "power_in"))
      (node (ref "JP1") (pin "VCC") (pinfunction "4_VCC") (pintype "passive"))
      (node (ref "JP2") (pin "2") (pinfunction "2_2") (pintype "passive"))
      (node (ref "R1") (pin "P$2") (pinfunction "2_P$2") (pintype "passive"))
      (node (ref "R8") (pin "P$2") (pinfunction "2_P$2") (pintype "passive"))
      (node (ref "SV1") (pin "3") (pinfunction "3_3") (pintype "passive"))
      (node (ref "SV11") (pin "2") (pinfunction "2_2") (pintype "passive"))
      (node (ref "SV11") (pin "4") (pinfunction "4_4") (pintype "passive"))
      (node (ref "SV11") (pin "6") (pinfunction "6_6") (pintype "passive"))
      (node (ref "SV11") (pin "8") (pinfunction "8_8") (pintype "passive"))
      (node (ref "U1") (pin "20") (pinfunction "AVCC_20") (pintype "bidirectional"))
      (node (ref "U1") (pin "7") (pinfunction "VCC_7") (pintype "bidirectional"))
      (node (ref "U2") (pin "21") (pinfunction "VCC_21") (pintype "bidirectional"))
      (node (ref "U3") (pin "21") (pinfunction "VCC_21") (pintype "bidirectional"))
      (node (ref "U4") (pin "21") (pinfunction "VCC_21") (pintype "bidirectional"))
    )
    (net (code "110") (name "unconnected-(IC3A-CLK-Pad2)") (class "Default")
      (node (ref "IC3") (pin "2") (pinfunction "CLK_2") (pintype "input"))
    )
    (net (code "111") (name "unconnected-(IC3A-INH-Pad15)") (class "Default")
      (node (ref "IC3") (pin "15") (pinfunction "INH_15") (pintype "input"))
    )
    (net (code "112") (name "unconnected-(IC3A-SH{slash}~{LD}-Pad1)") (class "Default")
      (node (ref "IC3") (pin "1") (pinfunction "SH/~{LD}_1") (pintype "input"))
    )
    (net (code "113") (name "unconnected-(IC3A-~{QH}-Pad7)") (class "Default")
      (node (ref "IC3") (pin "7") (pinfunction "~{QH}_7") (pintype "output"))
    )
    (net (code "114") (name "unconnected-(IC4A-QH-Pad9)") (class "Default")
      (node (ref "IC4") (pin "9") (pinfunction "QH_9") (pintype "output"))
    )
    (net (code "115") (name "unconnected-(IC4A-~{QH}-Pad7)") (class "Default")
      (node (ref "IC4") (pin "7") (pinfunction "~{QH}_7") (pintype "output"))
    )
    (net (code "116") (name "unconnected-(IC5A-CLR-Pad9)") (class "Default")
      (node (ref "IC5") (pin "9") (pinfunction "CLR_9") (pintype "input"))
    )
    (net (code "117") (name "unconnected-(JP1-1-PadDTR)") (class "Default")
      (node (ref "JP1") (pin "DTR") (pinfunction "1_DTR") (pintype "passive"))
    )
    (net (code "118") (name "unconnected-(JP1-5-PadCTS)") (class "Default")
      (node (ref "JP1") (pin "CTS") (pinfunction "5_CTS") (pintype "passive"))
    )
    (net (code "119") (name "unconnected-(S1-Pad1)") (class "Default")
      (node (ref "S1") (pin "1") (pinfunction "1_1") (pintype "passive"))
    )
    (net (code "120") (name "unconnected-(S1-Pad3)") (class "Default")
      (node (ref "S1") (pin "3") (pinfunction "3_3") (pintype "passive"))
    )
    (net (code "121") (name "unconnected-(U1-AREF-Pad21)") (class "Default")
      (node (ref "U1") (pin "21") (pinfunction "AREF_21") (pintype "bidirectional"))
    )
    (net (code "122") (name "unconnected-(U1-PB1(OC1A)-Pad15)") (class "Default")
      (node (ref "U1") (pin "15") (pinfunction "PB1(OC1A)_15") (pintype "bidirectional"))
    )
    (net (code "123") (name "unconnected-(U1-PC0(ADC0)-Pad23)") (class "Default")
      (node (ref "U1") (pin "23") (pinfunction "PC0(ADC0)_23") (pintype "bidirectional"))
    )
    (net (code "124") (name "unconnected-(U1-PC1(ADC1)-Pad24)") (class "Default")
      (node (ref "U1") (pin "24") (pinfunction "PC1(ADC1)_24") (pintype "bidirectional"))
    )
    (net (code "125") (name "unconnected-(U1-PC2(ADC2)-Pad25)") (class "Default")
      (node (ref "U1") (pin "25") (pinfunction "PC2(ADC2)_25") (pintype "bidirectional"))
    )
    (net (code "126") (name "unconnected-(U1-PC3(ADC3)-Pad26)") (class "Default")
      (node (ref "U1") (pin "26") (pinfunction "PC3(ADC3)_26") (pintype "bidirectional"))
    )
    (net (code "127") (name "unconnected-(U1-PD2(INT0)-Pad4)") (class "Default")
      (node (ref "U1") (pin "4") (pinfunction "PD2(INT0)_4") (pintype "bidirectional"))
    )
    (net (code "128") (name "unconnected-(U2-XERR-Pad16)") (class "Default")
      (node (ref "U2") (pin "16") (pinfunction "XERR_16") (pintype "bidirectional"))
    )
    (net (code "129") (name "unconnected-(U3-XERR-Pad16)") (class "Default")
      (node (ref "U3") (pin "16") (pinfunction "XERR_16") (pintype "bidirectional"))
    )
    (net (code "130") (name "unconnected-(U4-SOUT-Pad17)") (class "Default")
      (node (ref "U4") (pin "17") (pinfunction "SOUT_17") (pintype "bidirectional"))
    )
    (net (code "131") (name "unconnected-(U4-XERR-Pad16)") (class "Default")
      (node (ref "U4") (pin "16") (pinfunction "XERR_16") (pintype "bidirectional"))
    )
  )
)
